# SIM800L_SMD_0603.net
KiCad netlist of a schematic drawn in EAGLE
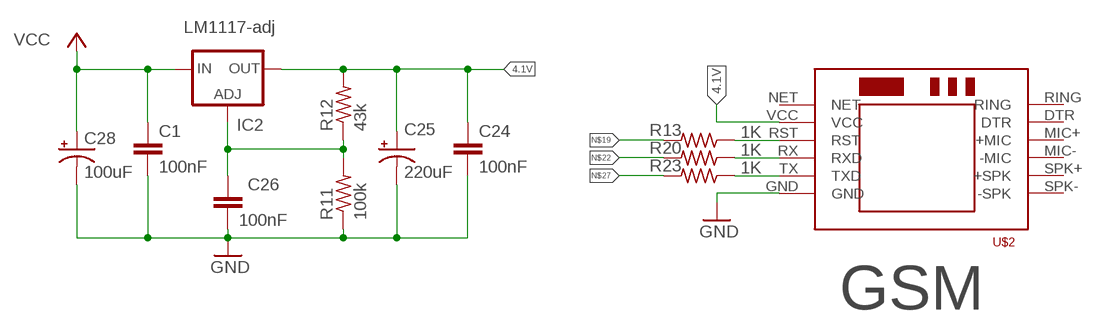
[diagram p0: schematic, sheet 1]

(export (version "E")
  (design (tool "Eeschema 10.0.6"))
  (components
    (comp (ref "C1")
      (value "100nF")
      (footprint "eagle-import:C0603")
      (libsource (lib "eagle-import") (part "C-EUC0603"))
    )
    (comp (ref "C24")
      (value "100nF")
      (footprint "eagle-import:C0603")
      (libsource (lib "eagle-import") (part "C-EUC0603"))
    )
    (comp (ref "C25")
      (value "220uF")
      (footprint "eagle-import:UD-6,3X7,7_NICHICON")
      (libsource (lib "eagle-import") (part "CPOL-USUD-6,3X7,7"))
    )
    (comp (ref "C26")
      (value "100nF")
      (footprint "eagle-import:C0603")
      (libsource (lib "eagle-import") (part "C-EUC0603"))
    )
    (comp (ref "C28")
      (value "100uF")
      (footprint "eagle-import:UD-6,3X7,7_NICHICON")
      (libsource (lib "eagle-import") (part "CPOL-USUD-6,3X7,7"))
    )
    (comp (ref "IC2")
      (value "LM1117-adj")
      (footprint "eagle-import:SOT223")
      (libsource (lib "eagle-import") (part "LD117A?S25TR"))
    )
    (comp (ref "R11")
      (value "100k")
      (footprint "eagle-import:R0603")
      (libsource (lib "eagle-import") (part "R-US_R0603"))
    )
    (comp (ref "R12")
      (value "43k")
      (footprint "eagle-import:R0603")
      (libsource (lib "eagle-import") (part "R-US_R0603"))
    )
    (comp (ref "R13")
      (value "1K")
      (footprint "eagle-import:R0603")
      (libsource (lib "eagle-import") (part "R-US_R0603"))
    )
    (comp (ref "R20")
      (value "1K")
      (footprint "eagle-import:R0603")
      (libsource (lib "eagle-import") (part "R-US_R0603"))
    )
    (comp (ref "R23")
      (value "1K")
      (footprint "eagle-import:R0603")
      (libsource (lib "eagle-import") (part "R-US_R0603"))
    )
    (comp (ref "U$2")
      (value "SIM800LMODULE")
      (footprint "eagle-import:SIM800LMODULE")
      (libsource (lib "eagle-import") (part "SIM800LMODULE"))
    )
  )
  (nets
    (net (code "1") (name "4.1V") (class "Default")
      (node (ref "C24") (pin "1") (pinfunction "1_1") (pintype "passive"))
      (node (ref "C25") (pin "+") (pinfunction "+_+") (pintype "passive"))
      (node (ref "IC2") (pin "4") (pinfunction "OUT_4") (pintype "passive"))
      (node (ref "R12") (pin "2") (pinfunction "2_2") (pintype "passive"))
      (node (ref "U$2") (pin "VCC") (pinfunction "VCC_VCC") (pintype "bidirectional"))
    )
    (net (code "2") (name "GND") (class "Default")
      (node (ref "C1") (pin "2") (pinfunction "2_2") (pintype "passive"))
      (node (ref "C24") (pin "2") (pinfunction "2_2") (pintype "passive"))
      (node (ref "C25") (pin "-") (pinfunction "-_-") (pintype "passive"))
      (node (ref "C26") (pin "2") (pinfunction "2_2") (pintype "passive"))
      (node (ref "C28") (pin "-") (pinfunction "-_-") (pintype "passive"))
      (node (ref "R11") (pin "1") (pinfunction "1_1") (pintype "passive"))
      (node (ref "U$2") (pin "GND") (pinfunction "GND_GND") (pintype "bidirectional"))
    )
    (net (code "3") (name "N$19") (class "Default")
      (node (ref "R13") (pin "2") (pinfunction "2_2") (pintype "passive"))
    )
    (net (code "4") (name "N$22") (class "Default")
      (node (ref "R20") (pin "2") (pinfunction "2_2") (pintype "passive"))
    )
    (net (code "5") (name "N$27") (class "Default")
      (node (ref "R23") (pin "2") (pinfunction "2_2") (pintype "passive"))
    )
    (net (code "6") (name "Net-(IC2-ADJ)") (class "Default")
      (node (ref "C26") (pin "1") (pinfunction "1_1") (pintype "passive"))
      (node (ref "IC2") (pin "1") (pinfunction "ADJ_1") (pintype "input"))
      (node (ref "R11") (pin "2") (pinfunction "2_2") (pintype "passive"))
      (node (ref "R12") (pin "1") (pinfunction "1_1") (pintype "passive"))
    )
    (net (code "7") (name "Net-(R13-Pad1)") (class "Default")
      (node (ref "R13") (pin "1") (pinfunction "1_1") (pintype "passive"))
      (node (ref "U$2") (pin "RST") (pinfunction "RST_RST") (pintype "bidirectional"))
    )
    (net (code "8") (name "Net-(U$2-RXD)") (class "Default")
      (node (ref "R20") (pin "1") (pinfunction "1_1") (pintype "passive"))
      (node (ref "U$2") (pin "RX") (pinfunction "RXD_RX") (pintype "bidirectional"))
    )
    (net (code "9") (name "Net-(U$2-TXD)") (class "Default")
      (node (ref "R23") (pin "1") (pinfunction "1_1") (pintype "passive"))
      (node (ref "U$2") (pin "TX") (pinfunction "TXD_TX") (pintype "bidirectional"))
    )
    (net (code "10") (name "VCC") (class "Default")
      (node (ref "C1") (pin "1") (pinfunction "1_1") (pintype "passive"))
      (node (ref "C28") (pin "+") (pinfunction "+_+") (pintype "passive"))
      (node (ref "IC2") (pin "3") (pinfunction "IN_3") (pintype "input"))
    )
    (net (code "11") (name "unconnected-(U$2-+MIC-PadMIC+)") (class "Default")
      (node (ref "U$2") (pin "MIC+") (pinfunction "+MIC_MIC+") (pintype "bidirectional"))
    )
    (net (code "12") (name "unconnected-(U$2-+SPK-PadSPK+)") (class "Default")
      (node (ref "U$2") (pin "SPK+") (pinfunction "+SPK_SPK+") (pintype "bidirectional"))
    )
    (net (code "13") (name "unconnected-(U$2--MIC-PadMIC-)") (class "Default")
      (node (ref "U$2") (pin "MIC-") (pinfunction "-MIC_MIC-") (pintype "bidirectional"))
    )
    (net (code "14") (name "unconnected-(U$2--SPK-PadSPK-)") (class "Default")
      (node (ref "U$2") (pin "SPK-") (pinfunction "-SPK_SPK-") (pintype "bidirectional"))
    )
    (net (code "15") (name "unconnected-(U$2-PadDTR)") (class "Default")
      (node (ref "U$2") (pin "DTR") (pinfunction "DTR_DTR") (pintype "bidirectional"))
    )
    (net (code "16") (name "unconnected-(U$2-PadNET)") (class "Default")
      (node (ref "U$2") (pin "NET") (pinfunction "NET_NET") (pintype "bidirectional"))
    )
    (net (code "17") (name "unconnected-(U$2-PadRING)") (class "Default")
      (node (ref "U$2") (pin "RING") (pinfunction "RING_RING") (pintype "bidirectional"))
    )
  )
)
